# Robo_Creative_Lab_9.net
KiCad netlist of a schematic drawn in EAGLE
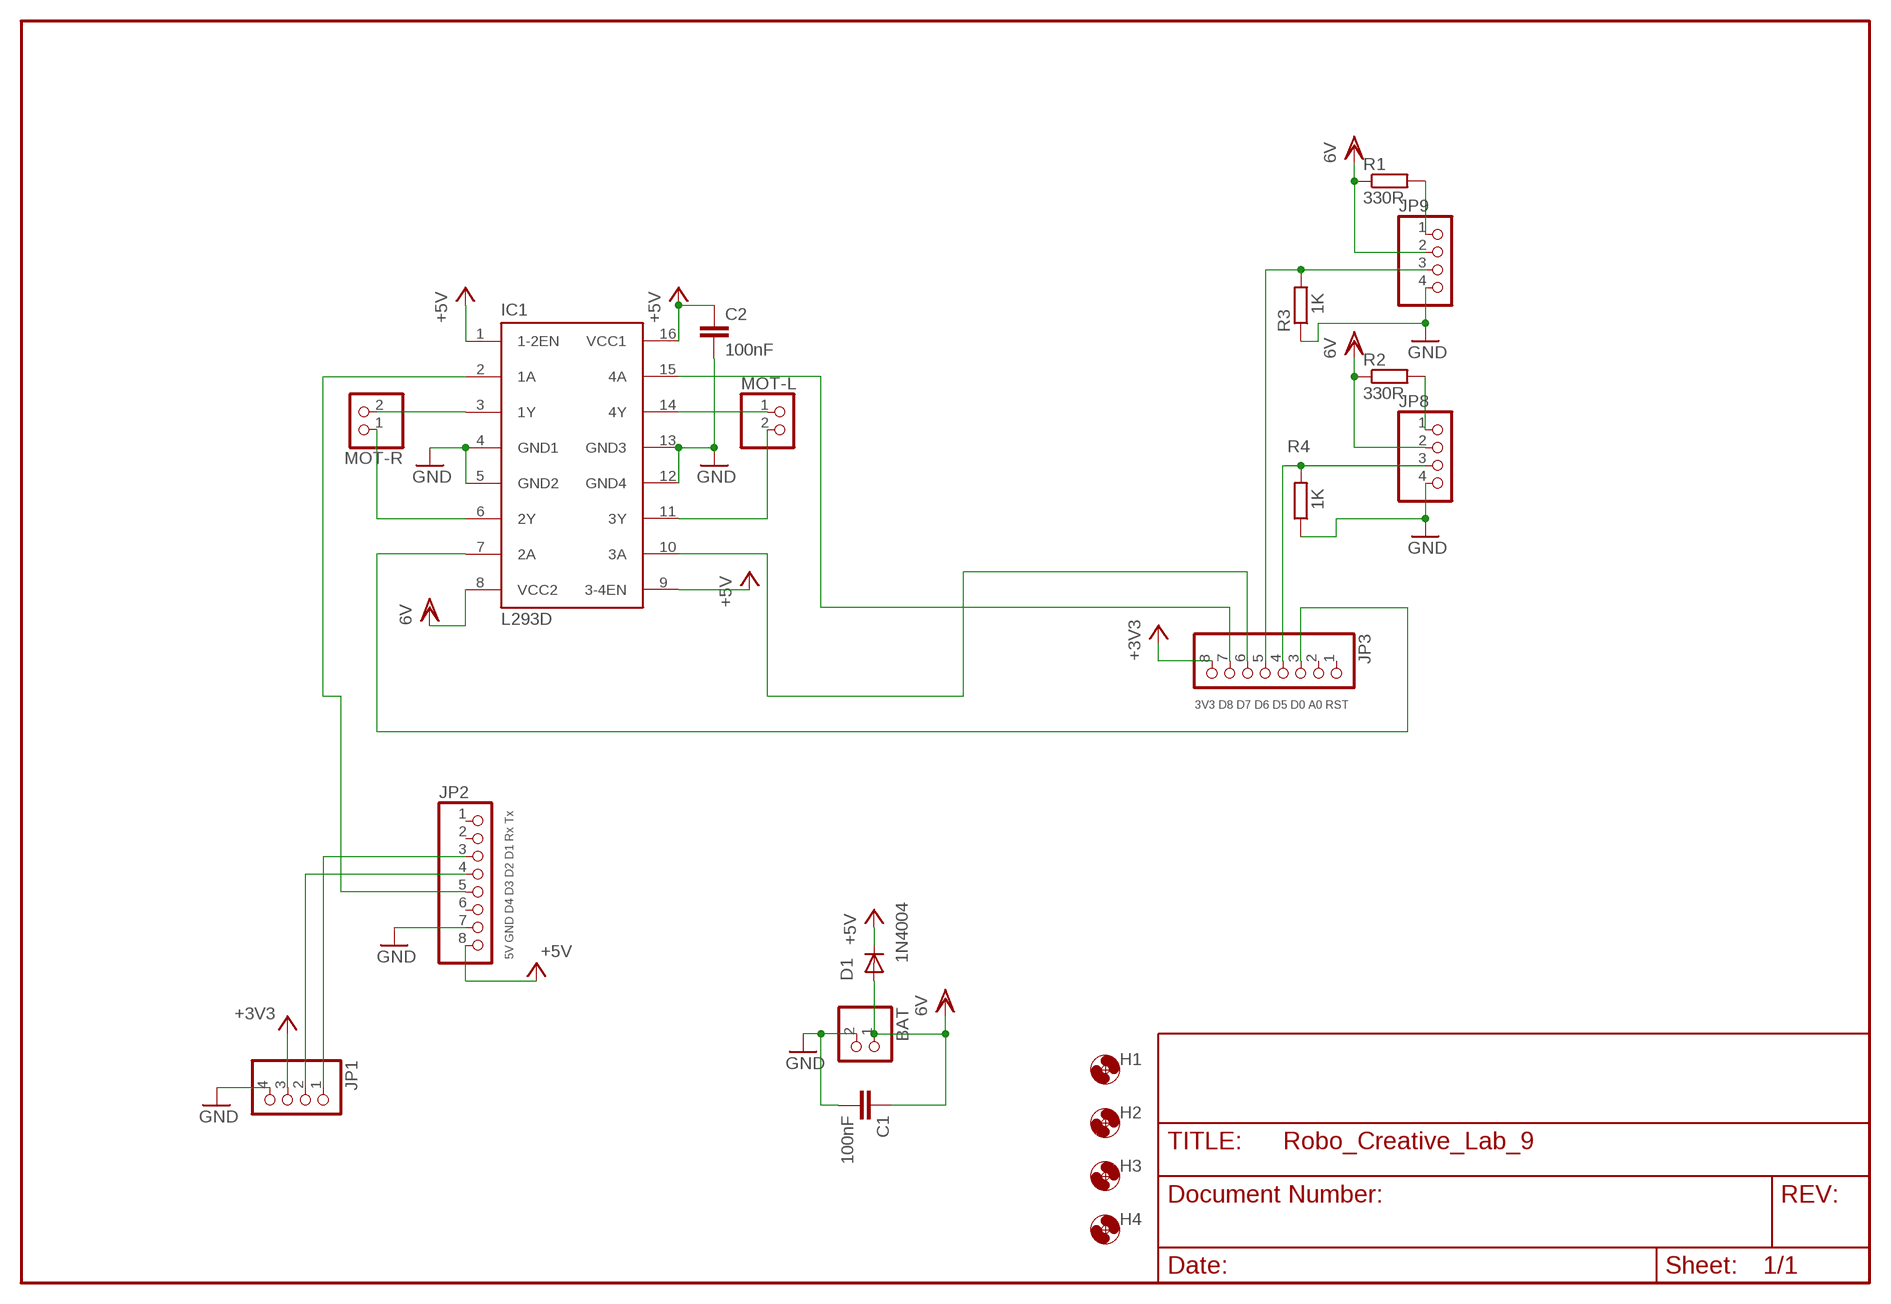
[diagram p0: schematic, sheet 1]

(export (version "E")
  (design (tool "Eeschema 10.0.6"))
  (components
    (comp (ref "BAT")
      (value "PINHD-1X2")
      (footprint "eagle-import:1X02")
      (libsource (lib "eagle-import") (part "PINHD-1X2"))
    )
    (comp (ref "C1")
      (value "100nF")
      (footprint "eagle-import:C050-025X075")
      (libsource (lib "eagle-import") (part "C-EU050-025X075"))
    )
    (comp (ref "C2")
      (value "100nF")
      (footprint "eagle-import:C050-025X075")
      (libsource (lib "eagle-import") (part "C-EU050-025X075"))
    )
    (comp (ref "D1")
      (value "1N4004")
      (footprint "eagle-import:DO41-10")
      (libsource (lib "eagle-import") (part "1N4004"))
    )
    (comp (ref "H1")
      (value "MOUNT-HOLE3.2")
      (footprint "eagle-import:3,2")
      (libsource (lib "eagle-import") (part "MOUNT-HOLE3.2"))
    )
    (comp (ref "H2")
      (value "MOUNT-HOLE3.2")
      (footprint "eagle-import:3,2")
      (libsource (lib "eagle-import") (part "MOUNT-HOLE3.2"))
    )
    (comp (ref "H3")
      (value "MOUNT-HOLE3.2")
      (footprint "eagle-import:3,2")
      (libsource (lib "eagle-import") (part "MOUNT-HOLE3.2"))
    )
    (comp (ref "H4")
      (value "MOUNT-HOLE3.2")
      (footprint "eagle-import:3,2")
      (libsource (lib "eagle-import") (part "MOUNT-HOLE3.2"))
    )
    (comp (ref "IC1")
      (value "L293D")
      (footprint "eagle-import:DIL16")
      (libsource (lib "eagle-import") (part "L293D"))
    )
    (comp (ref "JP1")
      (value "PINHD-1X4")
      (footprint "eagle-import:1X04")
      (libsource (lib "eagle-import") (part "PINHD-1X4"))
    )
    (comp (ref "JP2")
      (value "PINHD-1X8")
      (footprint "eagle-import:1X08")
      (libsource (lib "eagle-import") (part "PINHD-1X8"))
    )
    (comp (ref "JP3")
      (value "PINHD-1X8")
      (footprint "eagle-import:1X08")
      (libsource (lib "eagle-import") (part "PINHD-1X8"))
    )
    (comp (ref "JP8")
      (value "PINHD-1X4")
      (footprint "eagle-import:1X04")
      (libsource (lib "eagle-import") (part "PINHD-1X4"))
    )
    (comp (ref "JP9")
      (value "PINHD-1X4")
      (footprint "eagle-import:1X04")
      (libsource (lib "eagle-import") (part "PINHD-1X4"))
    )
    (comp (ref "MOT-L")
      (value "PINHD-1X2")
      (footprint "eagle-import:1X02")
      (libsource (lib "eagle-import") (part "PINHD-1X2"))
    )
    (comp (ref "MOT-R")
      (value "PINHD-1X2")
      (footprint "eagle-import:1X02")
      (libsource (lib "eagle-import") (part "PINHD-1X2"))
    )
    (comp (ref "R1")
      (value "330R")
      (footprint "eagle-import:0207_10")
      (libsource (lib "eagle-import") (part "R-EU_0207/10"))
    )
    (comp (ref "R2")
      (value "330R")
      (footprint "eagle-import:0207_10")
      (libsource (lib "eagle-import") (part "R-EU_0207/10"))
    )
    (comp (ref "R3")
      (value "1K")
      (footprint "eagle-import:0207_10")
      (libsource (lib "eagle-import") (part "R-EU_0207/10"))
    )
    (comp (ref "R4")
      (value "1K")
      (footprint "eagle-import:0207_10")
      (libsource (lib "eagle-import") (part "R-EU_0207/10"))
    )
  )
  (nets
    (net (code "1") (name "+3V3") (class "Default")
      (node (ref "JP1") (pin "3") (pinfunction "3_3") (pintype "passive"))
      (node (ref "JP3") (pin "8") (pinfunction "8_8") (pintype "passive"))
    )
    (net (code "2") (name "+5V") (class "Default")
      (node (ref "C2") (pin "1") (pinfunction "1_1") (pintype "passive"))
      (node (ref "D1") (pin "C") (pinfunction "C_C") (pintype "passive"))
      (node (ref "IC1") (pin "1") (pinfunction "1-2EN_1") (pintype "input"))
      (node (ref "IC1") (pin "16") (pinfunction "VCC1_16") (pintype "power_in"))
      (node (ref "IC1") (pin "9") (pinfunction "3-4EN_9") (pintype "input"))
      (node (ref "JP2") (pin "8") (pinfunction "8_8") (pintype "passive"))
    )
    (net (code "3") (name "6V") (class "Default")
      (node (ref "BAT") (pin "1") (pinfunction "1_1") (pintype "passive"))
      (node (ref "C1") (pin "1") (pinfunction "1_1") (pintype "passive"))
      (node (ref "D1") (pin "A") (pinfunction "A_A") (pintype "passive"))
      (node (ref "IC1") (pin "8") (pinfunction "VCC2_8") (pintype "power_in"))
      (node (ref "JP8") (pin "2") (pinfunction "2_2") (pintype "passive"))
      (node (ref "JP9") (pin "2") (pinfunction "2_2") (pintype "passive"))
      (node (ref "R1") (pin "1") (pinfunction "1_1") (pintype "passive"))
      (node (ref "R2") (pin "1") (pinfunction "1_1") (pintype "passive"))
    )
    (net (code "4") (name "GND") (class "Default")
      (node (ref "BAT") (pin "2") (pinfunction "2_2") (pintype "passive"))
      (node (ref "C1") (pin "2") (pinfunction "2_2") (pintype "passive"))
      (node (ref "C2") (pin "2") (pinfunction "2_2") (pintype "passive"))
      (node (ref "IC1") (pin "12") (pinfunction "GND4_12") (pintype "power_in"))
      (node (ref "IC1") (pin "13") (pinfunction "GND3_13") (pintype "power_in"))
      (node (ref "IC1") (pin "4") (pinfunction "GND1_4") (pintype "power_in"))
      (node (ref "IC1") (pin "5") (pinfunction "GND2_5") (pintype "power_in"))
      (node (ref "JP1") (pin "4") (pinfunction "4_4") (pintype "passive"))
      (node (ref "JP2") (pin "7") (pinfunction "7_7") (pintype "passive"))
      (node (ref "JP8") (pin "4") (pinfunction "4_4") (pintype "passive"))
      (node (ref "JP9") (pin "4") (pinfunction "4_4") (pintype "passive"))
      (node (ref "R3") (pin "1") (pinfunction "1_1") (pintype "passive"))
      (node (ref "R4") (pin "1") (pinfunction "1_1") (pintype "passive"))
    )
    (net (code "5") (name "Net-(IC1-1A)") (class "Default")
      (node (ref "IC1") (pin "2") (pinfunction "1A_2") (pintype "input"))
      (node (ref "JP2") (pin "5") (pinfunction "5_5") (pintype "passive"))
    )
    (net (code "6") (name "Net-(IC1-1Y)") (class "Default")
      (node (ref "IC1") (pin "3") (pinfunction "1Y_3") (pintype "output"))
      (node (ref "MOT-R") (pin "2") (pinfunction "2_2") (pintype "passive"))
    )
    (net (code "7") (name "Net-(IC1-2A)") (class "Default")
      (node (ref "IC1") (pin "7") (pinfunction "2A_7") (pintype "input"))
      (node (ref "JP3") (pin "3") (pinfunction "3_3") (pintype "passive"))
    )
    (net (code "8") (name "Net-(IC1-2Y)") (class "Default")
      (node (ref "IC1") (pin "6") (pinfunction "2Y_6") (pintype "output"))
      (node (ref "MOT-R") (pin "1") (pinfunction "1_1") (pintype "passive"))
    )
    (net (code "9") (name "Net-(IC1-3A)") (class "Default")
      (node (ref "IC1") (pin "10") (pinfunction "3A_10") (pintype "input"))
      (node (ref "JP3") (pin "6") (pinfunction "6_6") (pintype "passive"))
    )
    (net (code "10") (name "Net-(IC1-3Y)") (class "Default")
      (node (ref "IC1") (pin "11") (pinfunction "3Y_11") (pintype "output"))
      (node (ref "MOT-L") (pin "2") (pinfunction "2_2") (pintype "passive"))
    )
    (net (code "11") (name "Net-(IC1-4A)") (class "Default")
      (node (ref "IC1") (pin "15") (pinfunction "4A_15") (pintype "input"))
      (node (ref "JP3") (pin "7") (pinfunction "7_7") (pintype "passive"))
    )
    (net (code "12") (name "Net-(IC1-4Y)") (class "Default")
      (node (ref "IC1") (pin "14") (pinfunction "4Y_14") (pintype "output"))
      (node (ref "MOT-L") (pin "1") (pinfunction "1_1") (pintype "passive"))
    )
    (net (code "13") (name "Net-(JP1-Pad1)") (class "Default")
      (node (ref "JP1") (pin "1") (pinfunction "1_1") (pintype "passive"))
      (node (ref "JP2") (pin "3") (pinfunction "3_3") (pintype "passive"))
    )
    (net (code "14") (name "Net-(JP1-Pad2)") (class "Default")
      (node (ref "JP1") (pin "2") (pinfunction "2_2") (pintype "passive"))
      (node (ref "JP2") (pin "4") (pinfunction "4_4") (pintype "passive"))
    )
    (net (code "15") (name "Net-(JP3-Pad4)") (class "Default")
      (node (ref "JP3") (pin "4") (pinfunction "4_4") (pintype "passive"))
      (node (ref "JP8") (pin "3") (pinfunction "3_3") (pintype "passive"))
      (node (ref "R4") (pin "2") (pinfunction "2_2") (pintype "passive"))
    )
    (net (code "16") (name "Net-(JP3-Pad5)") (class "Default")
      (node (ref "JP3") (pin "5") (pinfunction "5_5") (pintype "passive"))
      (node (ref "JP9") (pin "3") (pinfunction "3_3") (pintype "passive"))
      (node (ref "R3") (pin "2") (pinfunction "2_2") (pintype "passive"))
    )
    (net (code "17") (name "Net-(JP8-Pad1)") (class "Default")
      (node (ref "JP8") (pin "1") (pinfunction "1_1") (pintype "passive"))
      (node (ref "R2") (pin "2") (pinfunction "2_2") (pintype "passive"))
    )
    (net (code "18") (name "Net-(JP9-Pad1)") (class "Default")
      (node (ref "JP9") (pin "1") (pinfunction "1_1") (pintype "passive"))
      (node (ref "R1") (pin "2") (pinfunction "2_2") (pintype "passive"))
    )
    (net (code "19") (name "unconnected-(JP2-Pad1)") (class "Default")
      (node (ref "JP2") (pin "1") (pinfunction "1_1") (pintype "passive"))
    )
    (net (code "20") (name "unconnected-(JP2-Pad2)") (class "Default")
      (node (ref "JP2") (pin "2") (pinfunction "2_2") (pintype "passive"))
    )
    (net (code "21") (name "unconnected-(JP2-Pad6)") (class "Default")
      (node (ref "JP2") (pin "6") (pinfunction "6_6") (pintype "passive"))
    )
    (net (code "22") (name "unconnected-(JP3-Pad1)") (class "Default")
      (node (ref "JP3") (pin "1") (pinfunction "1_1") (pintype "passive"))
    )
    (net (code "23") (name "unconnected-(JP3-Pad2)") (class "Default")
      (node (ref "JP3") (pin "2") (pinfunction "2_2") (pintype "passive"))
    )
  )
)
